# 3_mcu.net
KiCad netlist of a schematic drawn in Altium Designer
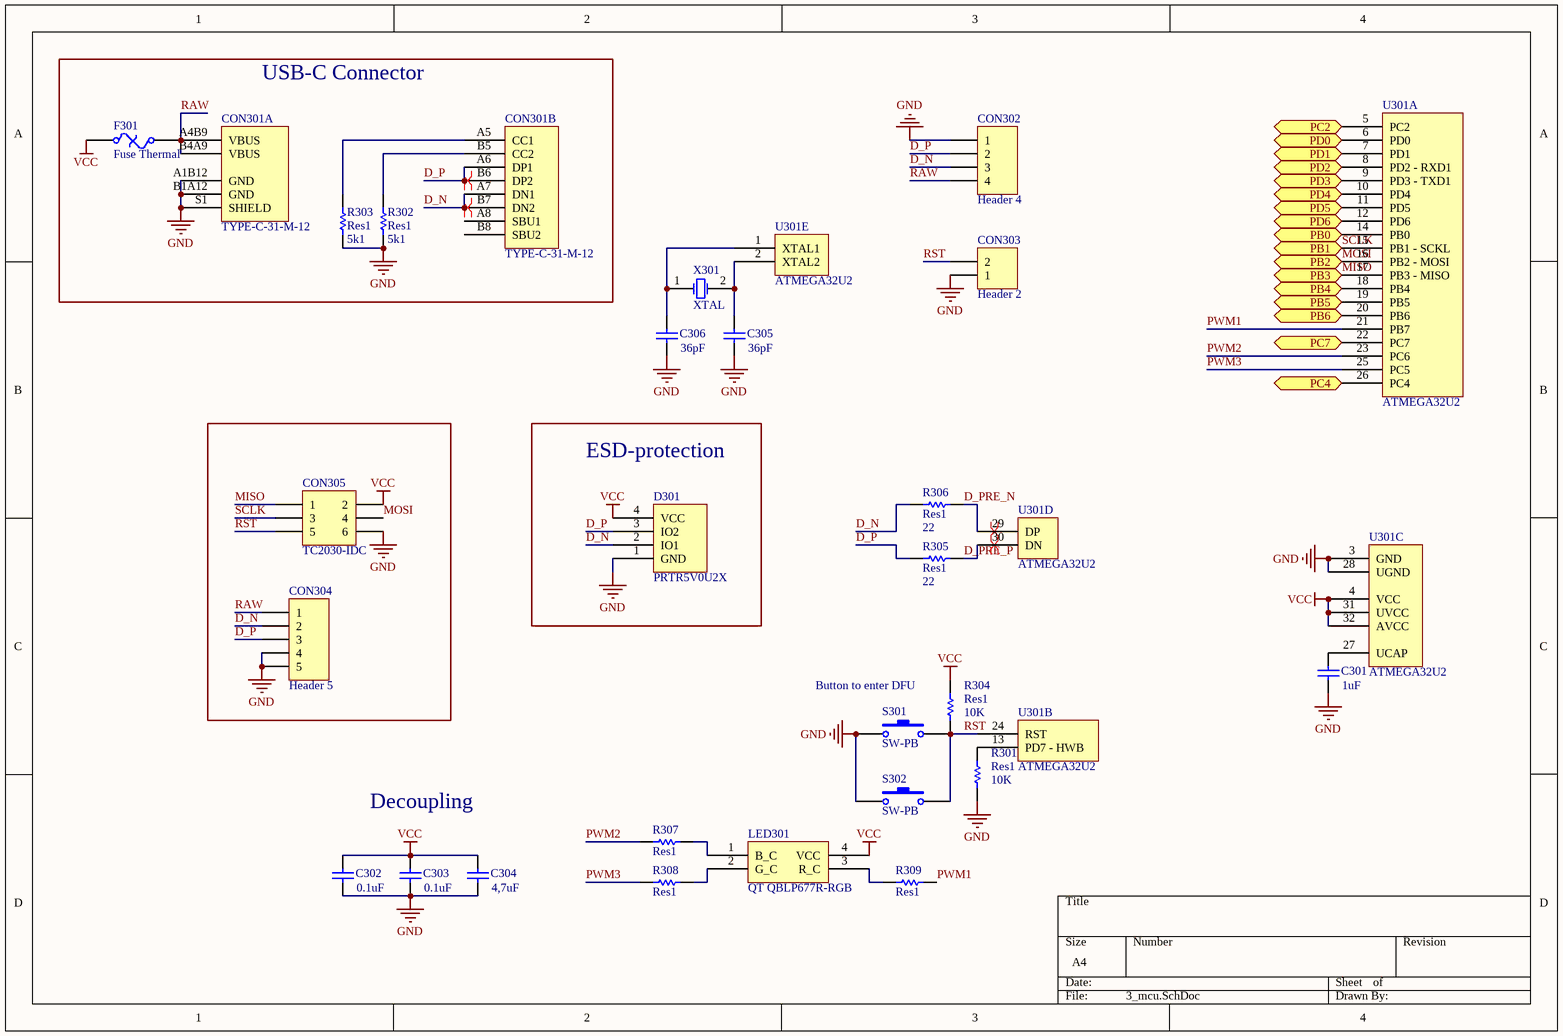
[diagram p0: 3_mcu.SchDoc]

(export (version "E")
  (design (tool "Eeschema 10.0.6"))
  (components
    (comp (ref "C301")
      (value "1uF")
      (footprint "C0603[1608]")
      (description "Capacitor")
      (fields (field (name "MFG") "KEMET") (field (name "MRF.PART") "CL10A105KB8NNNC"))
      (libsource (lib "Miscellaneous Devices") (part "Cap"))
    )
    (comp (ref "C302")
      (value "0.1uF")
      (footprint "C0603[1608]")
      (description "Capacitor")
      (fields (field (name "MFG") "KEMET") (field (name "MRF.PART") "CC0603KRX7R9BB104"))
      (libsource (lib "Miscellaneous Devices") (part "Cap"))
    )
    (comp (ref "C303")
      (value "0.1uF")
      (footprint "C0603[1608]")
      (description "Capacitor")
      (fields (field (name "MFG") "KEMET") (field (name "MRF.PART") "CC0603KRX7R9BB104"))
      (libsource (lib "Miscellaneous Devices") (part "Cap"))
    )
    (comp (ref "C304")
      (value "4,7uF")
      (footprint "C1206[3216]")
      (description "Capacitor")
      (fields (field (name "MFG") "KEMET") (field (name "MRF.PART") "1206B475K500NT"))
      (libsource (lib "Miscellaneous Devices") (part "Cap"))
    )
    (comp (ref "C305")
      (value "36pF")
      (footprint "C0603[1608]")
      (description "Capacitor")
      (fields (field (name "MFG") "KEMET") (field (name "MRF.PART") "CL10C360JB8NNNC"))
      (libsource (lib "Miscellaneous Devices") (part "Cap"))
    )
    (comp (ref "C306")
      (value "36pF")
      (footprint "C0603[1608]")
      (description "Capacitor")
      (fields (field (name "MFG") "KEMET") (field (name "MRF.PART") "CL10C360JB8NNNC"))
      (libsource (lib "Miscellaneous Devices") (part "Cap"))
    )
    (comp (ref "CON301")
      (value "TYPE-C-31-M-12")
      (footprint "TYPE-C-31-M-12")
      (fields (field (name "MFG") "Korean Hroparts Elec"))
      (libsource (lib "Schlib1") (part "TYPE-C-31-M-12"))
    )
    (comp (ref "CON302")
      (value "Header 4")
      (footprint "HDR1X4")
      (description "Header, 4-Pin")
      (libsource (lib "Miscellaneous Connectors") (part "Header 4"))
    )
    (comp (ref "CON303")
      (value "Header 2")
      (footprint "HDR1X2")
      (description "Header, 2-Pin")
      (libsource (lib "Miscellaneous Connectors") (part "Header 2"))
    )
    (comp (ref "CON304")
      (value "Header 5")
      (footprint "JST SM04B-SRSS-TB")
      (description "Header, 5-Pin")
      (fields (field (name "MFG") "JST Sales America Inc.") (field (name "MRF.PART") "SM04B-SRSS-TB(LF)(SN)"))
      (libsource (lib "Miscellaneous Connectors") (part "Header 5"))
    )
    (comp (ref "CON305")
      (value "TC2030-IDC")
      (footprint "TC2030-IDC-NL")
      (description "Header, 3-Pin, Dual row")
      (libsource (lib "Miscellaneous Connectors") (part "Header 3X2"))
    )
    (comp (ref "D301")
      (value "PRTR5V0U2X")
      (footprint "SOT190P237X120-4N")
      (fields (field (name "MFG") "Nexperia USA Inc.") (field (name "MRF.PART") "UET14A05L03"))
      (libsource (lib "Schlib1") (part "PRTR5V0U2X"))
    )
    (comp (ref "F301")
      (value "Fuse Thermal")
      (footprint "C1206[3216]")
      (description "Thermal Fuse")
      (fields (field (name "MFG") "Bel Fuse Inc.") (field (name "MRF.PART") "ASMD1206-050"))
      (libsource (lib "Miscellaneous Devices") (part "Fuse Thermal"))
    )
    (comp (ref "LED301")
      (value "QT QBLP677R-RGB")
      (footprint "QT QBLP677R-RGB")
      (libsource (lib "Keebs") (part "QT QBLP677R-RGB"))
    )
    (comp (ref "R301")
      (value "Res1")
      (footprint "R0603[1608]")
      (description "Resistor")
      (fields
        (field (name "ALTIUM_VALUE") "10K")
        (field (name "MFG") "Panasonic Electronic Components")
        (field (name "MRF.PART") "0603WAF1002T5E")
      )
      (libsource (lib "Miscellaneous Devices") (part "Res1"))
    )
    (comp (ref "R302")
      (value "Res1")
      (footprint "R0603[1608]")
      (description "Resistor")
      (fields
        (field (name "ALTIUM_VALUE") "5k1")
        (field (name "MFG") "Panasonic Electronic Components")
        (field (name "MRF.PART") "0603WAF5101T5E")
      )
      (libsource (lib "Miscellaneous Devices") (part "Res1"))
    )
    (comp (ref "R303")
      (value "Res1")
      (footprint "R0603[1608]")
      (description "Resistor")
      (fields
        (field (name "ALTIUM_VALUE") "5k1")
        (field (name "MFG") "Panasonic Electronic Components")
        (field (name "MRF.PART") "0603WAF5101T5E")
      )
      (libsource (lib "Miscellaneous Devices") (part "Res1"))
    )
    (comp (ref "R304")
      (value "Res1")
      (footprint "R0603[1608]")
      (description "Resistor")
      (fields
        (field (name "ALTIUM_VALUE") "10K")
        (field (name "MFG") "Panasonic Electronic Components")
        (field (name "MRF.PART") "0603WAF1002T5E")
      )
      (libsource (lib "Miscellaneous Devices") (part "Res1"))
    )
    (comp (ref "R305")
      (value "Res1")
      (footprint "R0603[1608]")
      (description "Resistor")
      (fields
        (field (name "ALTIUM_VALUE") "22")
        (field (name "MFG") "Panasonic Electronic Components")
        (field (name "MRF.PART") "0603WAF220JT5E")
      )
      (libsource (lib "Miscellaneous Devices") (part "Res1"))
    )
    (comp (ref "R306")
      (value "Res1")
      (footprint "R0603[1608]")
      (description "Resistor")
      (fields
        (field (name "ALTIUM_VALUE") "22")
        (field (name "MFG") "Panasonic Electronic Components")
        (field (name "MRF.PART") "0603WAF220JT5E")
      )
      (libsource (lib "Miscellaneous Devices") (part "Res1"))
    )
    (comp (ref "R307")
      (value "Res1")
      (footprint "R0603[1608]")
      (description "Resistor")
      (libsource (lib "Miscellaneous Devices") (part "Res1"))
    )
    (comp (ref "R308")
      (value "Res1")
      (footprint "R0603[1608]")
      (description "Resistor")
      (libsource (lib "Miscellaneous Devices") (part "Res1"))
    )
    (comp (ref "R309")
      (value "Res1")
      (footprint "R0603[1608]")
      (description "Resistor")
      (libsource (lib "Miscellaneous Devices") (part "Res1"))
    )
    (comp (ref "S301")
      (value "SW-PB")
      (footprint "430152050826")
      (description "Switch")
      (fields (field (name "MFG") "C&K") (field (name "MRF.PART") "TS-1187A-C-D-B"))
      (libsource (lib "Miscellaneous Devices") (part "SW-PB"))
    )
    (comp (ref "S302")
      (value "SW-PB")
      (footprint "430152050826")
      (description "Switch")
      (fields (field (name "MFG") "C&K") (field (name "MRF.PART") "TS-1187A-C-D-B"))
      (libsource (lib "Miscellaneous Devices") (part "SW-PB"))
    )
    (comp (ref "U301")
      (value "ATMEGA32U2")
      (footprint "ATMEGA32U2-COMBO")
      (fields (field (name "MFG") "Microchip Technology"))
      (libsource (lib "Keebs") (part "ATMEGA32U2"))
    )
    (comp (ref "X301")
      (value "XTAL")
      (footprint "CTS 445-series crystal")
      (description "Crystal Oscillator")
      (fields (field (name "MRF.PART") "X503216MSB2GI"))
      (libsource (lib "Miscellaneous Devices") (part "XTAL"))
    )
  )
  (nets
    (net (code "1") (name "/D_N") (class "Default")
      (node (ref "CON301") (pin "A7") (pinfunction "DN1_A7") (pintype "passive"))
      (node (ref "CON301") (pin "B7") (pinfunction "DN2_B7") (pintype "passive"))
      (node (ref "CON302") (pin "3") (pinfunction "3_3") (pintype "passive"))
      (node (ref "CON304") (pin "2") (pinfunction "2_2") (pintype "passive"))
      (node (ref "D301") (pin "2") (pinfunction "IO1_2") (pintype "passive"))
      (node (ref "R306") (pin "2") (pinfunction "2_2") (pintype "passive"))
    )
    (net (code "2") (name "/D_P") (class "Default")
      (node (ref "CON301") (pin "A6") (pinfunction "DP1_A6") (pintype "passive"))
      (node (ref "CON301") (pin "B6") (pinfunction "DP2_B6") (pintype "passive"))
      (node (ref "CON302") (pin "2") (pinfunction "2_2") (pintype "passive"))
      (node (ref "CON304") (pin "3") (pinfunction "3_3") (pintype "passive"))
      (node (ref "D301") (pin "3") (pinfunction "IO2_3") (pintype "passive"))
      (node (ref "R305") (pin "2") (pinfunction "2_2") (pintype "passive"))
    )
    (net (code "3") (name "/D_PRE_N") (class "Default")
      (node (ref "R306") (pin "1") (pinfunction "1_1") (pintype "passive"))
      (node (ref "U301") (pin "29") (pinfunction "DP_29") (pintype "passive"))
    )
    (net (code "4") (name "/D_PRE_P") (class "Default")
      (node (ref "R305") (pin "1") (pinfunction "1_1") (pintype "passive"))
      (node (ref "U301") (pin "30") (pinfunction "DN_30") (pintype "passive"))
    )
    (net (code "5") (name "/MISO") (class "Default")
      (node (ref "CON305") (pin "1") (pinfunction "1_1") (pintype "passive"))
      (node (ref "U301") (pin "17") (pinfunction "PB3_-_MISO_17") (pintype "passive"))
    )
    (net (code "6") (name "/MOSI") (class "Default")
      (node (ref "CON305") (pin "4") (pinfunction "4_4") (pintype "passive"))
      (node (ref "U301") (pin "16") (pinfunction "PB2_-_MOSI_16") (pintype "passive"))
    )
    (net (code "7") (name "/PB0") (class "Default")
      (node (ref "U301") (pin "14") (pinfunction "PB0_14") (pintype "passive"))
    )
    (net (code "8") (name "/PB4") (class "Default")
      (node (ref "U301") (pin "18") (pinfunction "PB4_18") (pintype "passive"))
    )
    (net (code "9") (name "/PB5") (class "Default")
      (node (ref "U301") (pin "19") (pinfunction "PB5_19") (pintype "passive"))
    )
    (net (code "10") (name "/PB6") (class "Default")
      (node (ref "U301") (pin "20") (pinfunction "PB6_20") (pintype "passive"))
    )
    (net (code "11") (name "/PC2") (class "Default")
      (node (ref "U301") (pin "5") (pinfunction "PC2_5") (pintype "passive"))
    )
    (net (code "12") (name "/PC4") (class "Default")
      (node (ref "U301") (pin "26") (pinfunction "PC4_26") (pintype "passive"))
    )
    (net (code "13") (name "/PC7") (class "Default")
      (node (ref "U301") (pin "22") (pinfunction "PC7_22") (pintype "passive"))
    )
    (net (code "14") (name "/PD0") (class "Default")
      (node (ref "U301") (pin "6") (pinfunction "PD0_6") (pintype "passive"))
    )
    (net (code "15") (name "/PD1") (class "Default")
      (node (ref "U301") (pin "7") (pinfunction "PD1_7") (pintype "passive"))
    )
    (net (code "16") (name "/PD2") (class "Default")
      (node (ref "U301") (pin "8") (pinfunction "PD2_-_RXD1_8") (pintype "passive"))
    )
    (net (code "17") (name "/PD3") (class "Default")
      (node (ref "U301") (pin "9") (pinfunction "PD3_-_TXD1_9") (pintype "passive"))
    )
    (net (code "18") (name "/PD4") (class "Default")
      (node (ref "U301") (pin "10") (pinfunction "PD4_10") (pintype "passive"))
    )
    (net (code "19") (name "/PD5") (class "Default")
      (node (ref "U301") (pin "11") (pinfunction "PD5_11") (pintype "passive"))
    )
    (net (code "20") (name "/PD6") (class "Default")
      (node (ref "U301") (pin "12") (pinfunction "PD6_12") (pintype "passive"))
    )
    (net (code "21") (name "/PWM1") (class "Default")
      (node (ref "R309") (pin "1") (pinfunction "1_1") (pintype "passive"))
      (node (ref "U301") (pin "21") (pinfunction "PB7_21") (pintype "passive"))
    )
    (net (code "22") (name "/PWM2") (class "Default")
      (node (ref "R307") (pin "2") (pinfunction "2_2") (pintype "passive"))
      (node (ref "U301") (pin "23") (pinfunction "PC6_23") (pintype "passive"))
    )
    (net (code "23") (name "/PWM3") (class "Default")
      (node (ref "R308") (pin "2") (pinfunction "2_2") (pintype "passive"))
      (node (ref "U301") (pin "25") (pinfunction "PC5_25") (pintype "passive"))
    )
    (net (code "24") (name "/RAW") (class "Default")
      (node (ref "CON301") (pin "A4B9") (pinfunction "VBUS_A4B9") (pintype "passive"))
      (node (ref "CON301") (pin "B4A9") (pinfunction "VBUS_B4A9") (pintype "passive"))
      (node (ref "CON302") (pin "4") (pinfunction "4_4") (pintype "passive"))
      (node (ref "CON304") (pin "1") (pinfunction "1_1") (pintype "passive"))
      (node (ref "F301") (pin "2") (pinfunction "2_2") (pintype "passive"))
    )
    (net (code "25") (name "/RST") (class "Default")
      (node (ref "CON303") (pin "2") (pinfunction "2_2") (pintype "passive"))
      (node (ref "CON305") (pin "5") (pinfunction "5_5") (pintype "passive"))
      (node (ref "R304") (pin "2") (pinfunction "2_2") (pintype "passive"))
      (node (ref "S301") (pin "1") (pinfunction "1_1") (pintype "passive"))
      (node (ref "S302") (pin "2") (pinfunction "2_2") (pintype "passive"))
      (node (ref "U301") (pin "24") (pinfunction "RST_24") (pintype "passive"))
    )
    (net (code "26") (name "/SCLK") (class "Default")
      (node (ref "CON305") (pin "3") (pinfunction "3_3") (pintype "passive"))
      (node (ref "U301") (pin "15") (pinfunction "PB1_-_SCKL_15") (pintype "passive"))
    )
    (net (code "27") (name "GND") (class "Default")
      (node (ref "C301") (pin "1") (pinfunction "1_1") (pintype "passive"))
      (node (ref "C302") (pin "1") (pinfunction "1_1") (pintype "passive"))
      (node (ref "C303") (pin "1") (pinfunction "1_1") (pintype "passive"))
      (node (ref "C304") (pin "1") (pinfunction "1_1") (pintype "passive"))
      (node (ref "C305") (pin "1") (pinfunction "1_1") (pintype "passive"))
      (node (ref "C306") (pin "1") (pinfunction "1_1") (pintype "passive"))
      (node (ref "CON301") (pin "A1B12") (pinfunction "GND_A1B12") (pintype "passive"))
      (node (ref "CON301") (pin "B1A12") (pinfunction "GND_B1A12") (pintype "passive"))
      (node (ref "CON301") (pin "S1") (pinfunction "SHIELD_S1") (pintype "passive"))
      (node (ref "CON302") (pin "1") (pinfunction "1_1") (pintype "passive"))
      (node (ref "CON303") (pin "1") (pinfunction "1_1") (pintype "passive"))
      (node (ref "CON304") (pin "4") (pinfunction "4_4") (pintype "passive"))
      (node (ref "CON304") (pin "5") (pinfunction "5_5") (pintype "passive"))
      (node (ref "CON305") (pin "6") (pinfunction "6_6") (pintype "passive"))
      (node (ref "D301") (pin "1") (pinfunction "GND_1") (pintype "passive"))
      (node (ref "R301") (pin "2") (pinfunction "2_2") (pintype "passive"))
      (node (ref "R302") (pin "2") (pinfunction "2_2") (pintype "passive"))
      (node (ref "R303") (pin "2") (pinfunction "2_2") (pintype "passive"))
      (node (ref "S301") (pin "2") (pinfunction "2_2") (pintype "passive"))
      (node (ref "S302") (pin "1") (pinfunction "1_1") (pintype "passive"))
      (node (ref "U301") (pin "28") (pinfunction "UGND_28") (pintype "passive"))
      (node (ref "U301") (pin "3") (pinfunction "GND_3") (pintype "passive"))
    )
    (net (code "28") (name "Net-(CON301B-CC1)") (class "Default")
      (node (ref "CON301") (pin "A5") (pinfunction "CC1_A5") (pintype "passive"))
      (node (ref "R303") (pin "1") (pinfunction "1_1") (pintype "passive"))
    )
    (net (code "29") (name "Net-(CON301B-CC2)") (class "Default")
      (node (ref "CON301") (pin "B5") (pinfunction "CC2_B5") (pintype "passive"))
      (node (ref "R302") (pin "1") (pinfunction "1_1") (pintype "passive"))
    )
    (net (code "30") (name "Net-(LED301-B_C)") (class "Default")
      (node (ref "LED301") (pin "1") (pinfunction "B_C_1") (pintype "passive"))
      (node (ref "R307") (pin "1") (pinfunction "1_1") (pintype "passive"))
    )
    (net (code "31") (name "Net-(LED301-G_C)") (class "Default")
      (node (ref "LED301") (pin "2") (pinfunction "G_C_2") (pintype "passive"))
      (node (ref "R308") (pin "1") (pinfunction "1_1") (pintype "passive"))
    )
    (net (code "32") (name "Net-(LED301-R_C)") (class "Default")
      (node (ref "LED301") (pin "3") (pinfunction "R_C_3") (pintype "passive"))
      (node (ref "R309") (pin "2") (pinfunction "2_2") (pintype "passive"))
    )
    (net (code "33") (name "Net-(U301B-PD7_-_HWB)") (class "Default")
      (node (ref "R301") (pin "1") (pinfunction "1_1") (pintype "passive"))
      (node (ref "U301") (pin "13") (pinfunction "PD7_-_HWB_13") (pintype "passive"))
    )
    (net (code "34") (name "Net-(U301C-UCAP)") (class "Default")
      (node (ref "C301") (pin "2") (pinfunction "2_2") (pintype "passive"))
      (node (ref "U301") (pin "27") (pinfunction "UCAP_27") (pintype "passive"))
    )
    (net (code "35") (name "Net-(U301E-XTAL1)") (class "Default")
      (node (ref "C306") (pin "2") (pinfunction "2_2") (pintype "passive"))
      (node (ref "U301") (pin "1") (pinfunction "XTAL1_1") (pintype "passive"))
      (node (ref "X301") (pin "1") (pinfunction "OSC1_1") (pintype "passive"))
    )
    (net (code "36") (name "Net-(U301E-XTAL2)") (class "Default")
      (node (ref "C305") (pin "2") (pinfunction "2_2") (pintype "passive"))
      (node (ref "U301") (pin "2") (pinfunction "XTAL2_2") (pintype "passive"))
      (node (ref "X301") (pin "2") (pinfunction "OSC2_2") (pintype "passive"))
    )
    (net (code "37") (name "VCC") (class "Default")
      (node (ref "C302") (pin "2") (pinfunction "2_2") (pintype "passive"))
      (node (ref "C303") (pin "2") (pinfunction "2_2") (pintype "passive"))
      (node (ref "C304") (pin "2") (pinfunction "2_2") (pintype "passive"))
      (node (ref "CON305") (pin "2") (pinfunction "2_2") (pintype "passive"))
      (node (ref "D301") (pin "4") (pinfunction "VCC_4") (pintype "passive"))
      (node (ref "F301") (pin "1") (pinfunction "1_1") (pintype "passive"))
      (node (ref "LED301") (pin "4") (pinfunction "VCC_4") (pintype "passive"))
      (node (ref "R304") (pin "1") (pinfunction "1_1") (pintype "passive"))
      (node (ref "U301") (pin "31") (pinfunction "UVCC_31") (pintype "passive"))
      (node (ref "U301") (pin "32") (pinfunction "AVCC_32") (pintype "passive"))
      (node (ref "U301") (pin "4") (pinfunction "VCC_4") (pintype "passive"))
    )
    (net (code "38") (name "unconnected-(CON301B-SBU1-PadA8)") (class "Default")
      (node (ref "CON301") (pin "A8") (pinfunction "SBU1_A8") (pintype "passive"))
    )
    (net (code "39") (name "unconnected-(CON301B-SBU2-PadB8)") (class "Default")
      (node (ref "CON301") (pin "B8") (pinfunction "SBU2_B8") (pintype "passive"))
    )
  )
)
